# weather_sensor_attiny85.net
KiCad netlist of a schematic drawn in EAGLE
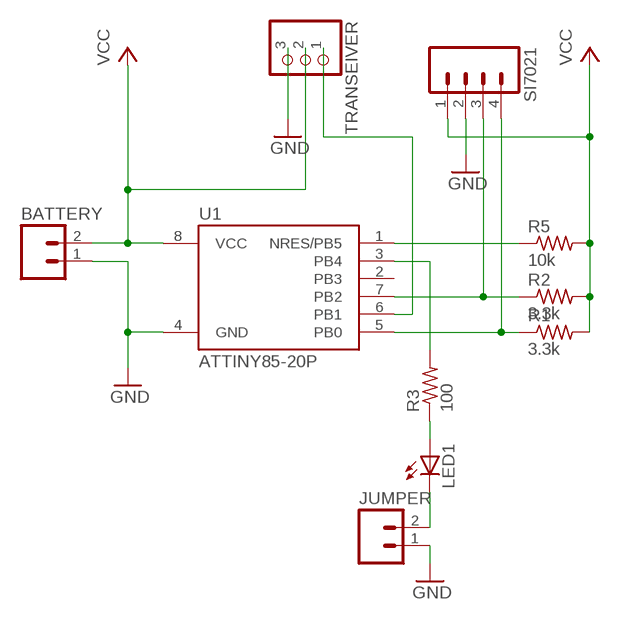
[diagram p0: schematic, sheet 1]

(export (version "E")
  (design (tool "Eeschema 10.0.6"))
  (components
    (comp (ref "BATTERY")
      (value "M02LOCK")
      (footprint "eagle-import:1X02_LOCK")
      (libsource (lib "eagle-import") (part "M02LOCK"))
    )
    (comp (ref "JUMPER")
      (value "M02LOCK")
      (footprint "eagle-import:1X02_LOCK")
      (libsource (lib "eagle-import") (part "M02LOCK"))
    )
    (comp (ref "LED1")
      (value "LEDCHIPLED_0603")
      (footprint "eagle-import:CHIPLED_0603")
      (libsource (lib "eagle-import") (part "LEDCHIPLED_0603"))
    )
    (comp (ref "R1")
      (value "3.3k")
      (footprint "eagle-import:R0402")
      (libsource (lib "eagle-import") (part "R-US_R0402"))
    )
    (comp (ref "R2")
      (value "3.3k")
      (footprint "eagle-import:R0402")
      (libsource (lib "eagle-import") (part "R-US_R0402"))
    )
    (comp (ref "R3")
      (value "100")
      (footprint "eagle-import:R0402")
      (libsource (lib "eagle-import") (part "R-US_R0402"))
    )
    (comp (ref "R5")
      (value "10k")
      (footprint "eagle-import:R0402")
      (libsource (lib "eagle-import") (part "R-US_R0402"))
    )
    (comp (ref "SI7021")
      (value "M04LONGPADS")
      (footprint "eagle-import:1X04_LONGPADS")
      (libsource (lib "eagle-import") (part "M04LONGPADS"))
    )
    (comp (ref "TRANSEIVER")
      (value "PINHD-1X3")
      (footprint "eagle-import:1X03")
      (libsource (lib "eagle-import") (part "PINHD-1X3"))
    )
    (comp (ref "U1")
      (value "ATTINY85-20P")
      (footprint "eagle-import:PDIP08_300MIL")
      (libsource (lib "eagle-import") (part "ATTINY85P-20"))
    )
  )
  (nets
    (net (code "1") (name "GND") (class "Default")
      (node (ref "BATTERY") (pin "1") (pinfunction "1_1") (pintype "passive"))
      (node (ref "JUMPER") (pin "1") (pinfunction "1_1") (pintype "passive"))
      (node (ref "SI7021") (pin "2") (pinfunction "2_2") (pintype "passive"))
      (node (ref "TRANSEIVER") (pin "3") (pinfunction "3_3") (pintype "passive"))
      (node (ref "U1") (pin "4") (pinfunction "GND_4") (pintype "power_in"))
    )
    (net (code "2") (name "Net-(JUMPER-Pad2)") (class "Default")
      (node (ref "JUMPER") (pin "2") (pinfunction "2_2") (pintype "passive"))
      (node (ref "LED1") (pin "C") (pinfunction "C_C") (pintype "passive"))
    )
    (net (code "3") (name "Net-(LED1-PadA)") (class "Default")
      (node (ref "LED1") (pin "A") (pinfunction "A_A") (pintype "passive"))
      (node (ref "R3") (pin "1") (pinfunction "1_1") (pintype "passive"))
    )
    (net (code "4") (name "Net-(U1-NRES{slash}PB5)") (class "Default")
      (node (ref "R5") (pin "1") (pinfunction "1_1") (pintype "passive"))
      (node (ref "U1") (pin "1") (pinfunction "NRES/PB5_1") (pintype "bidirectional"))
    )
    (net (code "5") (name "Net-(U1-PB0)") (class "Default")
      (node (ref "R1") (pin "1") (pinfunction "1_1") (pintype "passive"))
      (node (ref "SI7021") (pin "4") (pinfunction "4_4") (pintype "passive"))
      (node (ref "U1") (pin "5") (pinfunction "PB0_5") (pintype "bidirectional"))
    )
    (net (code "6") (name "Net-(U1-PB1)") (class "Default")
      (node (ref "TRANSEIVER") (pin "1") (pinfunction "1_1") (pintype "passive"))
      (node (ref "U1") (pin "6") (pinfunction "PB1_6") (pintype "bidirectional"))
    )
    (net (code "7") (name "Net-(U1-PB2)") (class "Default")
      (node (ref "R2") (pin "1") (pinfunction "1_1") (pintype "passive"))
      (node (ref "SI7021") (pin "3") (pinfunction "3_3") (pintype "passive"))
      (node (ref "U1") (pin "7") (pinfunction "PB2_7") (pintype "bidirectional"))
    )
    (net (code "8") (name "Net-(U1-PB4)") (class "Default")
      (node (ref "R3") (pin "2") (pinfunction "2_2") (pintype "passive"))
      (node (ref "U1") (pin "3") (pinfunction "PB4_3") (pintype "bidirectional"))
    )
    (net (code "9") (name "VCC") (class "Default")
      (node (ref "BATTERY") (pin "2") (pinfunction "2_2") (pintype "passive"))
      (node (ref "R1") (pin "2") (pinfunction "2_2") (pintype "passive"))
      (node (ref "R2") (pin "2") (pinfunction "2_2") (pintype "passive"))
      (node (ref "R5") (pin "2") (pinfunction "2_2") (pintype "passive"))
      (node (ref "SI7021") (pin "1") (pinfunction "1_1") (pintype "passive"))
      (node (ref "TRANSEIVER") (pin "2") (pinfunction "2_2") (pintype "passive"))
      (node (ref "U1") (pin "8") (pinfunction "VCC_8") (pintype "power_in"))
    )
    (net (code "10") (name "unconnected-(U1-PB3-Pad2)") (class "Default")
      (node (ref "U1") (pin "2") (pinfunction "PB3_2") (pintype "bidirectional"))
    )
  )
)
